# UWBNode_Sch.net
KiCad netlist of a schematic drawn in Altium Designer
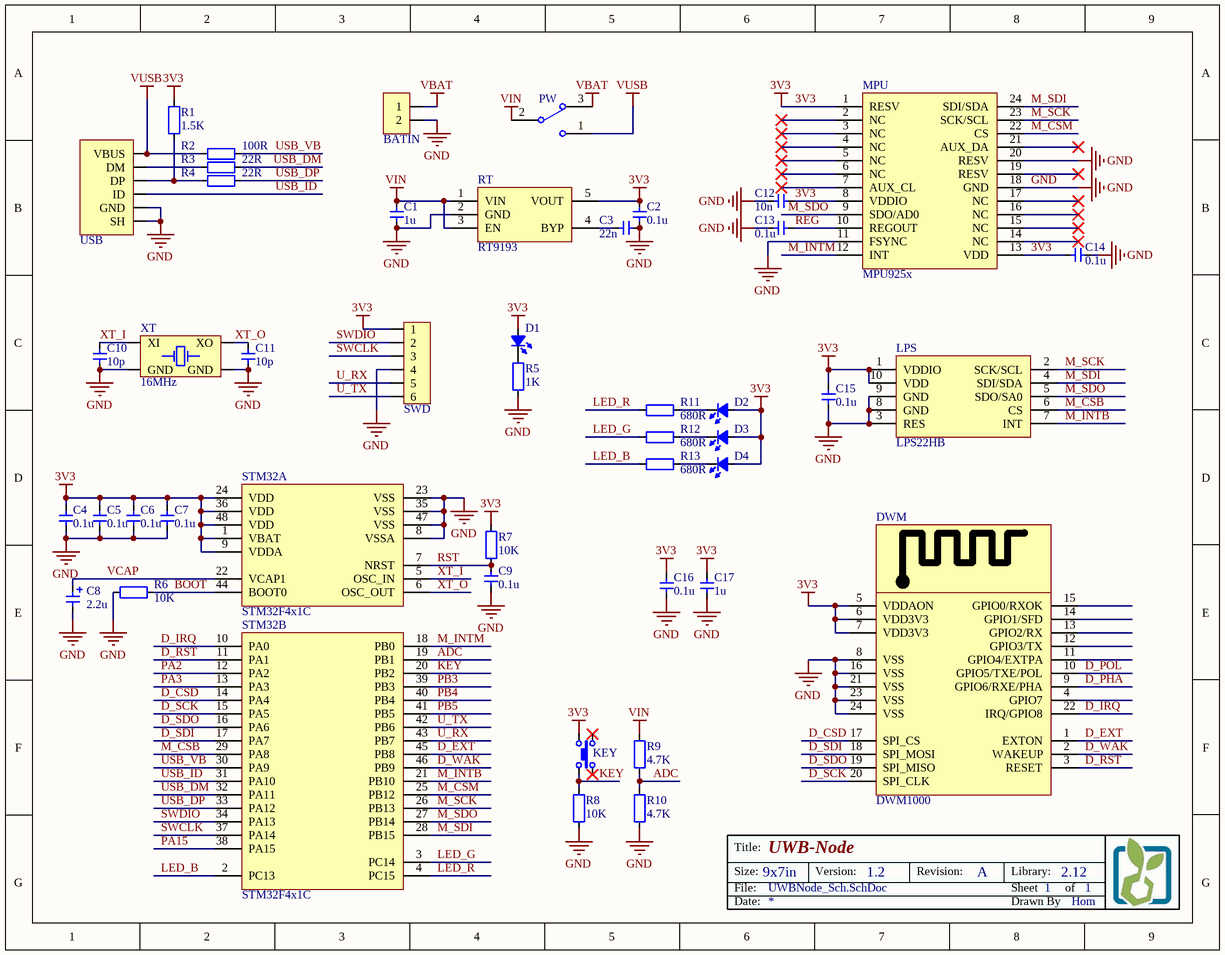
[diagram p0: UWBNode_Sch.SchDoc]

(export (version "E")
  (design (tool "Eeschema 10.0.6"))
  (components
    (comp (ref "BATIN")
      (value "MX1.25_2P")
      (footprint "PCB_Connector:MX1.25_S90_2P")
      (description "MX")
      (libsource (lib "SCH_Connector") (part "MX1.25_2P"))
    )
    (comp (ref "C1")
      (value "1u")
      (footprint "PCB_PassiveCap:CAP_0603")
      (description "Capacitor")
      (fields (field (name "Comment") "Cap_0603"))
      (libsource (lib "SCH_Passive") (part "Cap_0603"))
    )
    (comp (ref "C2")
      (value "0.1u")
      (footprint "PCB_PassiveCap:CAP_0603")
      (description "Capacitor")
      (fields (field (name "Comment") "Cap_0603"))
      (libsource (lib "SCH_Passive") (part "Cap_0603"))
    )
    (comp (ref "C3")
      (value "22n")
      (footprint "PCB_PassiveCap:CAP_0603")
      (description "Capacitor")
      (fields (field (name "Comment") "Cap_0603"))
      (libsource (lib "SCH_Passive") (part "Cap_0603"))
    )
    (comp (ref "C4")
      (value "0.1u")
      (footprint "PCB_PassiveCap:CAP_0603")
      (description "Capacitor")
      (fields (field (name "Comment") "Cap_0603"))
      (libsource (lib "SCH_Passive") (part "Cap_0603"))
    )
    (comp (ref "C5")
      (value "0.1u")
      (footprint "PCB_PassiveCap:CAP_0603")
      (description "Capacitor")
      (fields (field (name "Comment") "Cap_0603"))
      (libsource (lib "SCH_Passive") (part "Cap_0603"))
    )
    (comp (ref "C6")
      (value "0.1u")
      (footprint "PCB_PassiveCap:CAP_0603")
      (description "Capacitor")
      (fields (field (name "Comment") "Cap_0603"))
      (libsource (lib "SCH_Passive") (part "Cap_0603"))
    )
    (comp (ref "C7")
      (value "0.1u")
      (footprint "PCB_PassiveCap:CAP_0603")
      (description "Capacitor")
      (fields (field (name "Comment") "Cap_0603"))
      (libsource (lib "SCH_Passive") (part "Cap_0603"))
    )
    (comp (ref "C8")
      (value "2.2u")
      (footprint "PCB_PassiveCap:CAP_TAN_P0805")
      (description "Capacitor")
      (fields (field (name "Comment") "Cap_Tan_0805"))
      (libsource (lib "SCH_Passive") (part "Cap_Tan_0805"))
    )
    (comp (ref "C9")
      (value "0.1u")
      (footprint "PCB_PassiveCap:CAP_0603")
      (description "Capacitor")
      (fields (field (name "Comment") "Cap_0603"))
      (libsource (lib "SCH_Passive") (part "Cap_0603"))
    )
    (comp (ref "C10")
      (value "10p")
      (footprint "PCB_PassiveCap:CAP_0603")
      (description "Capacitor")
      (fields (field (name "Comment") "Cap_0603"))
      (libsource (lib "SCH_Passive") (part "Cap_0603"))
    )
    (comp (ref "C11")
      (value "10p")
      (footprint "PCB_PassiveCap:CAP_0603")
      (description "Capacitor")
      (fields (field (name "Comment") "Cap_0603"))
      (libsource (lib "SCH_Passive") (part "Cap_0603"))
    )
    (comp (ref "C12")
      (value "10n")
      (footprint "PCB_PassiveCap:CAP_0603")
      (description "Capacitor")
      (fields (field (name "Comment") "Cap_0603"))
      (libsource (lib "SCH_Passive") (part "Cap_0603"))
    )
    (comp (ref "C13")
      (value "0.1u")
      (footprint "PCB_PassiveCap:CAP_0603")
      (description "Capacitor")
      (fields (field (name "Comment") "Cap_0603"))
      (libsource (lib "SCH_Passive") (part "Cap_0603"))
    )
    (comp (ref "C14")
      (value "0.1u")
      (footprint "PCB_PassiveCap:CAP_0603")
      (description "Capacitor")
      (fields (field (name "Comment") "Cap_0603"))
      (libsource (lib "SCH_Passive") (part "Cap_0603"))
    )
    (comp (ref "C15")
      (value "0.1u")
      (footprint "PCB_PassiveCap:CAP_0603")
      (description "Capacitor")
      (fields (field (name "Comment") "Cap_0603"))
      (libsource (lib "SCH_Passive") (part "Cap_0603"))
    )
    (comp (ref "C16")
      (value "0.1u")
      (footprint "PCB_PassiveCap:CAP_0603")
      (description "Capacitor")
      (fields (field (name "Comment") "Cap_0603"))
      (libsource (lib "SCH_Passive") (part "Cap_0603"))
    )
    (comp (ref "C17")
      (value "1u")
      (footprint "PCB_PassiveCap:CAP_0603")
      (description "Capacitor")
      (fields (field (name "Comment") "Cap_0603"))
      (libsource (lib "SCH_Passive") (part "Cap_0603"))
    )
    (comp (ref "D1")
      (value "LED_0603")
      (footprint "PCB_ActiveLED:LED_0603_YELLOW")
      (description "LED")
      (libsource (lib "SCH_Active") (part "LED_0603"))
    )
    (comp (ref "D2")
      (value "LED_0603")
      (footprint "PCB_ActiveLED:LED_0603_RED")
      (description "LED")
      (libsource (lib "SCH_Active") (part "LED_0603"))
    )
    (comp (ref "D3")
      (value "LED_0603")
      (footprint "PCB_ActiveLED:LED_0603_GREEN")
      (description "LED")
      (libsource (lib "SCH_Active") (part "LED_0603"))
    )
    (comp (ref "D4")
      (value "LED_0603")
      (footprint "PCB_ActiveLED:LED_0603_BLUE")
      (description "LED")
      (libsource (lib "SCH_Active") (part "LED_0603"))
    )
    (comp (ref "DWM")
      (value "DWM1000")
      (footprint "PCB_Module:DWM1000")
      (description "Module")
      (fields (field (name "MANUFACTURER") "Decawave Limited"))
      (libsource (lib "SCH_Module") (part "DWM1000"))
    )
    (comp (ref "KEY")
      (value "ButtonTACT")
      (footprint "PCB_Switch:ButtonTACT_3.5*3.55_90")
      (description "Button")
      (libsource (lib "SCH_Switch") (part "ButtonTACT"))
    )
    (comp (ref "LPS")
      (value "LPS22HB")
      (footprint "PCB_IntegratedCircuit:HCLGA-2x2_10")
      (description "Sensor Pressure")
      (libsource (lib "SCH_IntegratedCircuit") (part "LPS22HB"))
    )
    (comp (ref "MPU")
      (value "MPU925x")
      (footprint "PCB_IntegratedCircuit:QFN_P0.4_24")
      (description "Sensor Motion")
      (libsource (lib "SCH_IntegratedCircuit") (part "MPU925x"))
    )
    (comp (ref "PW")
      (value "SwitchSPDT_2.8x6.6_90")
      (footprint "PCB_Switch:SwitchSPDT_2.8X6.6_90")
      (description "Switch")
      (libsource (lib "SCH_Switch") (part "SwitchSPDT_2.8x6.6_90"))
    )
    (comp (ref "R1")
      (value "1.5K")
      (footprint "PCB_PassiveRes:RES_0603")
      (description "Resistor")
      (fields (field (name "Comment") "Res_0603"))
      (libsource (lib "SCH_Passive") (part "Res_0603"))
    )
    (comp (ref "R2")
      (value "100R")
      (footprint "PCB_PassiveRes:RES_0603")
      (description "Resistor")
      (fields (field (name "Comment") "Res_0603"))
      (libsource (lib "") (part "Res_0603_1"))
    )
    (comp (ref "R3")
      (value "22R")
      (footprint "PCB_PassiveRes:RES_0603")
      (description "Resistor")
      (fields (field (name "Comment") "Res_0603"))
      (libsource (lib "") (part "Res_0603_1"))
    )
    (comp (ref "R4")
      (value "22R")
      (footprint "PCB_PassiveRes:RES_0603")
      (description "Resistor")
      (fields (field (name "Comment") "Res_0603"))
      (libsource (lib "") (part "Res_0603_1"))
    )
    (comp (ref "R5")
      (value "1K")
      (footprint "PCB_PassiveRes:RES_0603")
      (description "Resistor")
      (fields (field (name "Comment") "Res_0603"))
      (libsource (lib "") (part "Res_0603_2"))
    )
    (comp (ref "R6")
      (value "10K")
      (footprint "PCB_PassiveRes:RES_0603")
      (description "Resistor")
      (fields (field (name "Comment") "Res_0603"))
      (libsource (lib "") (part "Res_0603_3"))
    )
    (comp (ref "R7")
      (value "10K")
      (footprint "PCB_PassiveRes:RES_0603")
      (description "Resistor")
      (fields (field (name "Comment") "Res_0603"))
      (libsource (lib "") (part "Res_0603_2"))
    )
    (comp (ref "R8")
      (value "10K")
      (footprint "PCB_PassiveRes:RES_0603")
      (description "Resistor")
      (fields (field (name "Comment") "Res_0603"))
      (libsource (lib "") (part "Res_0603_2"))
    )
    (comp (ref "R9")
      (value "4.7K")
      (footprint "PCB_PassiveRes:RES_0603")
      (description "Resistor")
      (fields (field (name "Comment") "Res_0603"))
      (libsource (lib "SCH_Passive") (part "Res_0603"))
    )
    (comp (ref "R10")
      (value "4.7K")
      (footprint "PCB_PassiveRes:RES_0603")
      (description "Resistor")
      (fields (field (name "Comment") "Res_0603"))
      (libsource (lib "SCH_Passive") (part "Res_0603"))
    )
    (comp (ref "R11")
      (value "680R")
      (footprint "PCB_PassiveRes:RES_0603")
      (description "Resistor")
      (fields (field (name "Comment") "Res_0603"))
      (libsource (lib "") (part "Res_0603_1"))
    )
    (comp (ref "R12")
      (value "680R")
      (footprint "PCB_PassiveRes:RES_0603")
      (description "Resistor")
      (fields (field (name "Comment") "Res_0603"))
      (libsource (lib "") (part "Res_0603_1"))
    )
    (comp (ref "R13")
      (value "680R")
      (footprint "PCB_PassiveRes:RES_0603")
      (description "Resistor")
      (fields (field (name "Comment") "Res_0603"))
      (libsource (lib "") (part "Res_0603_1"))
    )
    (comp (ref "RT")
      (value "RT9193")
      (footprint "PCB_IntegratedCircuit:SOT23-5")
      (description "Power")
      (libsource (lib "SCH_IntegratedCircuit") (part "RT9193"))
    )
    (comp (ref "STM32")
      (value "STM32F4x1C")
      (footprint "PCB_IntegratedCircuit:QFN_P0.5_48")
      (description "MCU")
      (libsource (lib "SCH_IntegratedCircuit") (part "STM32F4x1C"))
    )
    (comp (ref "SWD")
      (value "HDR1x6_1.27")
      (footprint "PCB_ConnectorHDR:HDR1X6_1.27_180HFD")
      (description "Header")
      (libsource (lib "SCH_ConnectorHDR") (part "HDR1x6_1.27"))
    )
    (comp (ref "USB")
      (value "USB_Micro")
      (footprint "PCB_USB:USB_Micro-AB")
      (description "USB")
      (libsource (lib "SCH_USB") (part "USB_Micro"))
    )
    (comp (ref "XT")
      (value "16MHz")
      (footprint "PCB_Oscillator:XT_2520_4")
      (description "Crystal Oscillator")
      (fields (field (name "Comment") "XTAL_2520_4P"))
      (libsource (lib "SCH_Oscillator") (part "XTAL_2520_4P"))
    )
  )
  (nets
    (net (code "1") (name "/ADC") (class "Default")
      (node (ref "R10") (pin "1") (pinfunction "1_1") (pintype "passive"))
      (node (ref "R9") (pin "2") (pinfunction "2_2") (pintype "passive"))
      (node (ref "STM32") (pin "19") (pinfunction "PB1_19") (pintype "passive"))
    )
    (net (code "2") (name "/BOOT") (class "Default")
      (node (ref "R6") (pin "2") (pinfunction "2_2") (pintype "passive"))
      (node (ref "STM32") (pin "44") (pinfunction "BOOT0_44") (pintype "passive"))
    )
    (net (code "3") (name "/D_CSD") (class "Default")
      (node (ref "DWM") (pin "17") (pinfunction "SPI_CS_17") (pintype "passive"))
      (node (ref "STM32") (pin "14") (pinfunction "PA4_14") (pintype "passive"))
    )
    (net (code "4") (name "/D_EXT") (class "Default")
      (node (ref "DWM") (pin "1") (pinfunction "EXTON_1") (pintype "passive"))
      (node (ref "STM32") (pin "45") (pinfunction "PB8_45") (pintype "passive"))
    )
    (net (code "5") (name "/D_IRQ") (class "Default")
      (node (ref "DWM") (pin "22") (pinfunction "IRQ/GPIO8_22") (pintype "passive"))
      (node (ref "STM32") (pin "10") (pinfunction "PA0_10") (pintype "passive"))
    )
    (net (code "6") (name "/D_PHA") (class "Default")
      (node (ref "DWM") (pin "9") (pinfunction "GPIO6/RXE/PHA_9") (pintype "passive"))
    )
    (net (code "7") (name "/D_POL") (class "Default")
      (node (ref "DWM") (pin "10") (pinfunction "GPIO5/TXE/POL_10") (pintype "passive"))
    )
    (net (code "8") (name "/D_RST") (class "Default")
      (node (ref "DWM") (pin "3") (pinfunction "RESET_3") (pintype "passive"))
      (node (ref "STM32") (pin "11") (pinfunction "PA1_11") (pintype "passive"))
    )
    (net (code "9") (name "/D_SCK") (class "Default")
      (node (ref "DWM") (pin "20") (pinfunction "SPI_CLK_20") (pintype "passive"))
      (node (ref "STM32") (pin "15") (pinfunction "PA5_15") (pintype "passive"))
    )
    (net (code "10") (name "/D_SDI") (class "Default")
      (node (ref "DWM") (pin "18") (pinfunction "SPI_MOSI_18") (pintype "passive"))
      (node (ref "STM32") (pin "17") (pinfunction "PA7_17") (pintype "passive"))
    )
    (net (code "11") (name "/D_SDO") (class "Default")
      (node (ref "DWM") (pin "19") (pinfunction "SPI_MISO_19") (pintype "passive"))
      (node (ref "STM32") (pin "16") (pinfunction "PA6_16") (pintype "passive"))
    )
    (net (code "12") (name "/D_WAK") (class "Default")
      (node (ref "DWM") (pin "2") (pinfunction "WAKEUP_2") (pintype "passive"))
      (node (ref "STM32") (pin "46") (pinfunction "PB9_46") (pintype "passive"))
    )
    (net (code "13") (name "/KEY") (class "Default")
      (node (ref "KEY") (pin "1") (pinfunction "1_1") (pintype "passive"))
      (node (ref "R8") (pin "2") (pinfunction "2_2") (pintype "passive"))
      (node (ref "STM32") (pin "20") (pinfunction "PB2_20") (pintype "passive"))
    )
    (net (code "14") (name "/LED_B") (class "Default")
      (node (ref "R13") (pin "2") (pinfunction "2_2") (pintype "passive"))
      (node (ref "STM32") (pin "2") (pinfunction "PC13_2") (pintype "passive"))
    )
    (net (code "15") (name "/LED_G") (class "Default")
      (node (ref "R12") (pin "2") (pinfunction "2_2") (pintype "passive"))
      (node (ref "STM32") (pin "3") (pinfunction "PC14_3") (pintype "passive"))
    )
    (net (code "16") (name "/LED_R") (class "Default")
      (node (ref "R11") (pin "2") (pinfunction "2_2") (pintype "passive"))
      (node (ref "STM32") (pin "4") (pinfunction "PC15_4") (pintype "passive"))
    )
    (net (code "17") (name "/M_CSB") (class "Default")
      (node (ref "LPS") (pin "6") (pinfunction "CS_6") (pintype "passive"))
      (node (ref "STM32") (pin "29") (pinfunction "PA8_29") (pintype "passive"))
    )
    (net (code "18") (name "/M_CSM") (class "Default")
      (node (ref "MPU") (pin "22") (pinfunction "CS_22") (pintype "passive"))
      (node (ref "STM32") (pin "25") (pinfunction "PB12_25") (pintype "passive"))
    )
    (net (code "19") (name "/M_INTB") (class "Default")
      (node (ref "LPS") (pin "7") (pinfunction "INT_7") (pintype "passive"))
      (node (ref "STM32") (pin "21") (pinfunction "PB10_21") (pintype "passive"))
    )
    (net (code "20") (name "/M_INTM") (class "Default")
      (node (ref "MPU") (pin "12") (pinfunction "INT_12") (pintype "passive"))
      (node (ref "STM32") (pin "18") (pinfunction "PB0_18") (pintype "passive"))
    )
    (net (code "21") (name "/M_SCK") (class "Default")
      (node (ref "LPS") (pin "2") (pinfunction "SCK/SCL_2") (pintype "passive"))
      (node (ref "MPU") (pin "23") (pinfunction "SCK/SCL_23") (pintype "passive"))
      (node (ref "STM32") (pin "26") (pinfunction "PB13_26") (pintype "passive"))
    )
    (net (code "22") (name "/M_SDI") (class "Default")
      (node (ref "LPS") (pin "4") (pinfunction "SDI/SDA_4") (pintype "passive"))
      (node (ref "MPU") (pin "24") (pinfunction "SDI/SDA_24") (pintype "passive"))
      (node (ref "STM32") (pin "28") (pinfunction "PB15_28") (pintype "passive"))
    )
    (net (code "23") (name "/M_SDO") (class "Default")
      (node (ref "LPS") (pin "5") (pinfunction "SDO/SA0_5") (pintype "passive"))
      (node (ref "MPU") (pin "9") (pinfunction "SDO/AD0_9") (pintype "passive"))
      (node (ref "STM32") (pin "27") (pinfunction "PB14_27") (pintype "passive"))
    )
    (net (code "24") (name "/PA2") (class "Default")
      (node (ref "STM32") (pin "12") (pinfunction "PA2_12") (pintype "passive"))
    )
    (net (code "25") (name "/PA3") (class "Default")
      (node (ref "STM32") (pin "13") (pinfunction "PA3_13") (pintype "passive"))
    )
    (net (code "26") (name "/PA15") (class "Default")
      (node (ref "STM32") (pin "38") (pinfunction "PA15_38") (pintype "passive"))
    )
    (net (code "27") (name "/PB3") (class "Default")
      (node (ref "STM32") (pin "39") (pinfunction "PB3_39") (pintype "passive"))
    )
    (net (code "28") (name "/PB4") (class "Default")
      (node (ref "STM32") (pin "40") (pinfunction "PB4_40") (pintype "passive"))
    )
    (net (code "29") (name "/PB5") (class "Default")
      (node (ref "STM32") (pin "41") (pinfunction "PB5_41") (pintype "passive"))
    )
    (net (code "30") (name "/REG") (class "Default")
      (node (ref "C13") (pin "2") (pinfunction "2_2") (pintype "passive"))
      (node (ref "MPU") (pin "10") (pinfunction "REGOUT_10") (pintype "passive"))
    )
    (net (code "31") (name "/RST") (class "Default")
      (node (ref "C9") (pin "2") (pinfunction "2_2") (pintype "passive"))
      (node (ref "R7") (pin "1") (pinfunction "1_1") (pintype "passive"))
      (node (ref "STM32") (pin "7") (pinfunction "NRST_7") (pintype "passive"))
    )
    (net (code "32") (name "/SWCLK") (class "Default")
      (node (ref "STM32") (pin "37") (pinfunction "PA14_37") (pintype "passive"))
      (node (ref "SWD") (pin "3") (pinfunction "3_3") (pintype "passive"))
    )
    (net (code "33") (name "/SWDIO") (class "Default")
      (node (ref "STM32") (pin "34") (pinfunction "PA13_34") (pintype "passive"))
      (node (ref "SWD") (pin "2") (pinfunction "2_2") (pintype "passive"))
    )
    (net (code "34") (name "/USB_DM") (class "Default")
      (node (ref "R3") (pin "1") (pinfunction "1_1") (pintype "passive"))
      (node (ref "STM32") (pin "32") (pinfunction "PA11_32") (pintype "passive"))
    )
    (net (code "35") (name "/USB_DP") (class "Default")
      (node (ref "R4") (pin "1") (pinfunction "1_1") (pintype "passive"))
      (node (ref "STM32") (pin "33") (pinfunction "PA12_33") (pintype "passive"))
    )
    (net (code "36") (name "/USB_ID") (class "Default")
      (node (ref "STM32") (pin "31") (pinfunction "PA10_31") (pintype "passive"))
      (node (ref "USB") (pin "4") (pinfunction "ID_4") (pintype "passive"))
    )
    (net (code "37") (name "/USB_VB") (class "Default")
      (node (ref "R2") (pin "1") (pinfunction "1_1") (pintype "passive"))
      (node (ref "STM32") (pin "30") (pinfunction "PA9_30") (pintype "passive"))
    )
    (net (code "38") (name "/U_RX") (class "Default")
      (node (ref "STM32") (pin "43") (pinfunction "PB7_43") (pintype "passive"))
      (node (ref "SWD") (pin "5") (pinfunction "5_5") (pintype "passive"))
    )
    (net (code "39") (name "/U_TX") (class "Default")
      (node (ref "STM32") (pin "42") (pinfunction "PB6_42") (pintype "passive"))
      (node (ref "SWD") (pin "6") (pinfunction "6_6") (pintype "passive"))
    )
    (net (code "40") (name "/VCAP") (class "Default")
      (node (ref "C8") (pin "1") (pinfunction "1_1") (pintype "passive"))
      (node (ref "STM32") (pin "22") (pinfunction "VCAP1_22") (pintype "passive"))
    )
    (net (code "41") (name "/XT_I") (class "Default")
      (node (ref "C10") (pin "2") (pinfunction "2_2") (pintype "passive"))
      (node (ref "STM32") (pin "5") (pinfunction "OSC_IN_5") (pintype "passive"))
      (node (ref "XT") (pin "1") (pinfunction "XI_1") (pintype "passive"))
    )
    (net (code "42") (name "/XT_O") (class "Default")
      (node (ref "C11") (pin "2") (pinfunction "2_2") (pintype "passive"))
      (node (ref "STM32") (pin "6") (pinfunction "OSC_OUT_6") (pintype "passive"))
      (node (ref "XT") (pin "3") (pinfunction "XO_3") (pintype "passive"))
    )
    (net (code "43") (name "3V3") (class "Default")
      (node (ref "C12") (pin "2") (pinfunction "2_2") (pintype "passive"))
      (node (ref "C14") (pin "2") (pinfunction "2_2") (pintype "passive"))
      (node (ref "C15") (pin "1") (pinfunction "1_1") (pintype "passive"))
      (node (ref "C16") (pin "1") (pinfunction "1_1") (pintype "passive"))
      (node (ref "C17") (pin "1") (pinfunction "1_1") (pintype "passive"))
      (node (ref "C2") (pin "2") (pinfunction "2_2") (pintype "passive"))
      (node (ref "C4") (pin "1") (pinfunction "1_1") (pintype "passive"))
      (node (ref "C5") (pin "1") (pinfunction "1_1") (pintype "passive"))
      (node (ref "C6") (pin "1") (pinfunction "1_1") (pintype "passive"))
      (node (ref "C7") (pin "1") (pinfunction "1_1") (pintype "passive"))
      (node (ref "D1") (pin "1") (pinfunction "A_1") (pintype "passive"))
      (node (ref "D2") (pin "1") (pinfunction "A_1") (pintype "passive"))
      (node (ref "D3") (pin "1") (pinfunction "A_1") (pintype "passive"))
      (node (ref "D4") (pin "1") (pinfunction "A_1") (pintype "passive"))
      (node (ref "DWM") (pin "5") (pinfunction "VDDAON_5") (pintype "passive"))
      (node (ref "DWM") (pin "6") (pinfunction "VDD3V3_6") (pintype "passive"))
      (node (ref "DWM") (pin "7") (pinfunction "VDD3V3_7") (pintype "passive"))
      (node (ref "KEY") (pin "2") (pinfunction "2_2") (pintype "passive"))
      (node (ref "LPS") (pin "1") (pinfunction "VDDIO_1") (pintype "passive"))
      (node (ref "LPS") (pin "10") (pinfunction "VDD_10") (pintype "passive"))
      (node (ref "MPU") (pin "1") (pinfunction "RESV_1") (pintype "passive"))
      (node (ref "MPU") (pin "13") (pinfunction "VDD_13") (pintype "passive"))
      (node (ref "MPU") (pin "8") (pinfunction "VDDIO_8") (pintype "passive"))
      (node (ref "R1") (pin "1") (pinfunction "1_1") (pintype "passive"))
      (node (ref "R7") (pin "2") (pinfunction "2_2") (pintype "passive"))
      (node (ref "RT") (pin "5") (pinfunction "VOUT_5") (pintype "passive"))
      (node (ref "STM32") (pin "1") (pinfunction "VBAT_1") (pintype "passive"))
      (node (ref "STM32") (pin "24") (pinfunction "VDD_24") (pintype "passive"))
      (node (ref "STM32") (pin "36") (pinfunction "VDD_36") (pintype "passive"))
      (node (ref "STM32") (pin "48") (pinfunction "VDD_48") (pintype "passive"))
      (node (ref "STM32") (pin "9") (pinfunction "VDDA_9") (pintype "passive"))
      (node (ref "SWD") (pin "1") (pinfunction "1_1") (pintype "passive"))
    )
    (net (code "44") (name "GND") (class "Default")
      (node (ref "BATIN") (pin "2") (pinfunction "2_2") (pintype "passive"))
      (node (ref "C1") (pin "1") (pinfunction "1_1") (pintype "passive"))
      (node (ref "C10") (pin "1") (pinfunction "1_1") (pintype "passive"))
      (node (ref "C11") (pin "1") (pinfunction "1_1") (pintype "passive"))
      (node (ref "C12") (pin "1") (pinfunction "1_1") (pintype "passive"))
      (node (ref "C13") (pin "1") (pinfunction "1_1") (pintype "passive"))
      (node (ref "C14") (pin "1") (pinfunction "1_1") (pintype "passive"))
      (node (ref "C15") (pin "2") (pinfunction "2_2") (pintype "passive"))
      (node (ref "C16") (pin "2") (pinfunction "2_2") (pintype "passive"))
      (node (ref "C17") (pin "2") (pinfunction "2_2") (pintype "passive"))
      (node (ref "C2") (pin "1") (pinfunction "1_1") (pintype "passive"))
      (node (ref "C3") (pin "1") (pinfunction "1_1") (pintype "passive"))
      (node (ref "C4") (pin "2") (pinfunction "2_2") (pintype "passive"))
      (node (ref "C5") (pin "2") (pinfunction "2_2") (pintype "passive"))
      (node (ref "C6") (pin "2") (pinfunction "2_2") (pintype "passive"))
      (node (ref "C7") (pin "2") (pinfunction "2_2") (pintype "passive"))
      (node (ref "C8") (pin "2") (pinfunction "2_2") (pintype "passive"))
      (node (ref "C9") (pin "1") (pinfunction "1_1") (pintype "passive"))
      (node (ref "DWM") (pin "16") (pinfunction "VSS_16") (pintype "passive"))
      (node (ref "DWM") (pin "21") (pinfunction "VSS_21") (pintype "passive"))
      (node (ref "DWM") (pin "23") (pinfunction "VSS_23") (pintype "passive"))
      (node (ref "DWM") (pin "24") (pinfunction "VSS_24") (pintype "passive"))
      (node (ref "DWM") (pin "8") (pinfunction "VSS_8") (pintype "passive"))
      (node (ref "LPS") (pin "3") (pinfunction "RES_3") (pintype "passive"))
      (node (ref "LPS") (pin "8") (pinfunction "GND_8") (pintype "passive"))
      (node (ref "LPS") (pin "9") (pinfunction "GND_9") (pintype "passive"))
      (node (ref "MPU") (pin "11") (pinfunction "FSYNC_11") (pintype "passive"))
      (node (ref "MPU") (pin "18") (pinfunction "GND_18") (pintype "passive"))
      (node (ref "MPU") (pin "20") (pinfunction "RESV_20") (pintype "passive"))
      (node (ref "R10") (pin "2") (pinfunction "2_2") (pintype "passive"))
      (node (ref "R5") (pin "1") (pinfunction "1_1") (pintype "passive"))
      (node (ref "R6") (pin "1") (pinfunction "1_1") (pintype "passive"))
      (node (ref "R8") (pin "1") (pinfunction "1_1") (pintype "passive"))
      (node (ref "RT") (pin "2") (pinfunction "GND_2") (pintype "passive"))
      (node (ref "STM32") (pin "23") (pinfunction "VSS_23") (pintype "passive"))
      (node (ref "STM32") (pin "35") (pinfunction "VSS_35") (pintype "passive"))
      (node (ref "STM32") (pin "47") (pinfunction "VSS_47") (pintype "passive"))
      (node (ref "STM32") (pin "8") (pinfunction "VSSA_8") (pintype "passive"))
      (node (ref "SWD") (pin "4") (pinfunction "4_4") (pintype "passive"))
      (node (ref "USB") (pin "0") (pinfunction "SH_0") (pintype "passive"))
      (node (ref "USB") (pin "5") (pinfunction "GND_5") (pintype "passive"))
      (node (ref "XT") (pin "2") (pinfunction "GND_2") (pintype "passive"))
      (node (ref "XT") (pin "4") (pinfunction "GND_4") (pintype "passive"))
    )
    (net (code "45") (name "Net-(D1-K)") (class "Default")
      (node (ref "D1") (pin "2") (pinfunction "K_2") (pintype "passive"))
      (node (ref "R5") (pin "2") (pinfunction "2_2") (pintype "passive"))
    )
    (net (code "46") (name "Net-(D2-K)") (class "Default")
      (node (ref "D2") (pin "2") (pinfunction "K_2") (pintype "passive"))
      (node (ref "R11") (pin "1") (pinfunction "1_1") (pintype "passive"))
    )
    (net (code "47") (name "Net-(D3-K)") (class "Default")
      (node (ref "D3") (pin "2") (pinfunction "K_2") (pintype "passive"))
      (node (ref "R12") (pin "1") (pinfunction "1_1") (pintype "passive"))
    )
    (net (code "48") (name "Net-(D4-K)") (class "Default")
      (node (ref "D4") (pin "2") (pinfunction "K_2") (pintype "passive"))
      (node (ref "R13") (pin "1") (pinfunction "1_1") (pintype "passive"))
    )
    (net (code "49") (name "Net-(RT-BYP)") (class "Default")
      (node (ref "C3") (pin "2") (pinfunction "2_2") (pintype "passive"))
      (node (ref "RT") (pin "4") (pinfunction "BYP_4") (pintype "passive"))
    )
    (net (code "50") (name "Net-(USB-DM)") (class "Default")
      (node (ref "R3") (pin "2") (pinfunction "2_2") (pintype "passive"))
      (node (ref "USB") (pin "2") (pinfunction "DM_2") (pintype "passive"))
    )
    (net (code "51") (name "Net-(USB-DP)") (class "Default")
      (node (ref "R1") (pin "2") (pinfunction "2_2") (pintype "passive"))
      (node (ref "R4") (pin "2") (pinfunction "2_2") (pintype "passive"))
      (node (ref "USB") (pin "3") (pinfunction "DP_3") (pintype "passive"))
    )
    (net (code "52") (name "VBAT") (class "Default")
      (node (ref "BATIN") (pin "1") (pinfunction "1_1") (pintype "passive"))
      (node (ref "PW") (pin "3") (pinfunction "3_3") (pintype "passive"))
    )
    (net (code "53") (name "VIN") (class "Default")
      (node (ref "C1") (pin "2") (pinfunction "2_2") (pintype "passive"))
      (node (ref "PW") (pin "2") (pinfunction "2_2") (pintype "passive"))
      (node (ref "R9") (pin "1") (pinfunction "1_1") (pintype "passive"))
      (node (ref "RT") (pin "1") (pinfunction "VIN_1") (pintype "passive"))
      (node (ref "RT") (pin "3") (pinfunction "EN_3") (pintype "power_in"))
    )
    (net (code "54") (name "VUSB") (class "Default")
      (node (ref "PW") (pin "1") (pinfunction "1_1") (pintype "passive"))
      (node (ref "R2") (pin "2") (pinfunction "2_2") (pintype "passive"))
      (node (ref "USB") (pin "1") (pinfunction "VBUS_1") (pintype "passive"))
    )
    (net (code "55") (name "unconnected-(DWM-GPIO0{slash}RXOK-Pad15)") (class "Default")
      (node (ref "DWM") (pin "15") (pinfunction "GPIO0/RXOK_15") (pintype "passive"))
    )
    (net (code "56") (name "unconnected-(DWM-GPIO1{slash}SFD-Pad14)") (class "Default")
      (node (ref "DWM") (pin "14") (pinfunction "GPIO1/SFD_14") (pintype "passive"))
    )
    (net (code "57") (name "unconnected-(DWM-GPIO2{slash}RX-Pad13)") (class "Default")
      (node (ref "DWM") (pin "13") (pinfunction "GPIO2/RX_13") (pintype "passive"))
    )
    (net (code "58") (name "unconnected-(DWM-GPIO3{slash}TX-Pad12)") (class "Default")
      (node (ref "DWM") (pin "12") (pinfunction "GPIO3/TX_12") (pintype "passive"))
    )
    (net (code "59") (name "unconnected-(DWM-GPIO4{slash}EXTPA-Pad11)") (class "Default")
      (node (ref "DWM") (pin "11") (pinfunction "GPIO4/EXTPA_11") (pintype "passive"))
    )
    (net (code "60") (name "unconnected-(DWM-GPIO7-Pad4)") (class "Default")
      (node (ref "DWM") (pin "4") (pinfunction "GPIO7_4") (pintype "passive"))
    )
    (net (code "61") (name "unconnected-(KEY-Pad3)") (class "Default")
      (node (ref "KEY") (pin "3") (pinfunction "3_3") (pintype "passive+no_connect"))
    )
    (net (code "62") (name "unconnected-(KEY-Pad4)") (class "Default")
      (node (ref "KEY") (pin "4") (pinfunction "4_4") (pintype "passive+no_connect"))
    )
    (net (code "63") (name "unconnected-(MPU-AUX_CL-Pad7)") (class "Default")
      (node (ref "MPU") (pin "7") (pinfunction "AUX_CL_7") (pintype "passive+no_connect"))
    )
    (net (code "64") (name "unconnected-(MPU-AUX_DA-Pad21)") (class "Default")
      (node (ref "MPU") (pin "21") (pinfunction "AUX_DA_21") (pintype "passive+no_connect"))
    )
    (net (code "65") (name "unconnected-(MPU-NC-Pad2)") (class "Default")
      (node (ref "MPU") (pin "2") (pinfunction "NC_2") (pintype "passive+no_connect"))
    )
    (net (code "66") (name "unconnected-(MPU-NC-Pad3)") (class "Default")
      (node (ref "MPU") (pin "3") (pinfunction "NC_3") (pintype "passive+no_connect"))
    )
    (net (code "67") (name "unconnected-(MPU-NC-Pad4)") (class "Default")
      (node (ref "MPU") (pin "4") (pinfunction "NC_4") (pintype "passive+no_connect"))
    )
    (net (code "68") (name "unconnected-(MPU-NC-Pad5)") (class "Default")
      (node (ref "MPU") (pin "5") (pinfunction "NC_5") (pintype "passive+no_connect"))
    )
    (net (code "69") (name "unconnected-(MPU-NC-Pad6)") (class "Default")
      (node (ref "MPU") (pin "6") (pinfunction "NC_6") (pintype "passive+no_connect"))
    )
    (net (code "70") (name "unconnected-(MPU-NC-Pad14)") (class "Default")
      (node (ref "MPU") (pin "14") (pinfunction "NC_14") (pintype "passive+no_connect"))
    )
    (net (code "71") (name "unconnected-(MPU-NC-Pad15)") (class "Default")
      (node (ref "MPU") (pin "15") (pinfunction "NC_15") (pintype "passive+no_connect"))
    )
    (net (code "72") (name "unconnected-(MPU-NC-Pad16)") (class "Default")
      (node (ref "MPU") (pin "16") (pinfunction "NC_16") (pintype "passive+no_connect"))
    )
    (net (code "73") (name "unconnected-(MPU-NC-Pad17)") (class "Default")
      (node (ref "MPU") (pin "17") (pinfunction "NC_17") (pintype "passive+no_connect"))
    )
    (net (code "74") (name "unconnected-(MPU-RESV-Pad19)") (class "Default")
      (node (ref "MPU") (pin "19") (pinfunction "RESV_19") (pintype "passive+no_connect"))
    )
  )
)
